# Power.net
KiCad netlist of a schematic drawn in Altium Designer
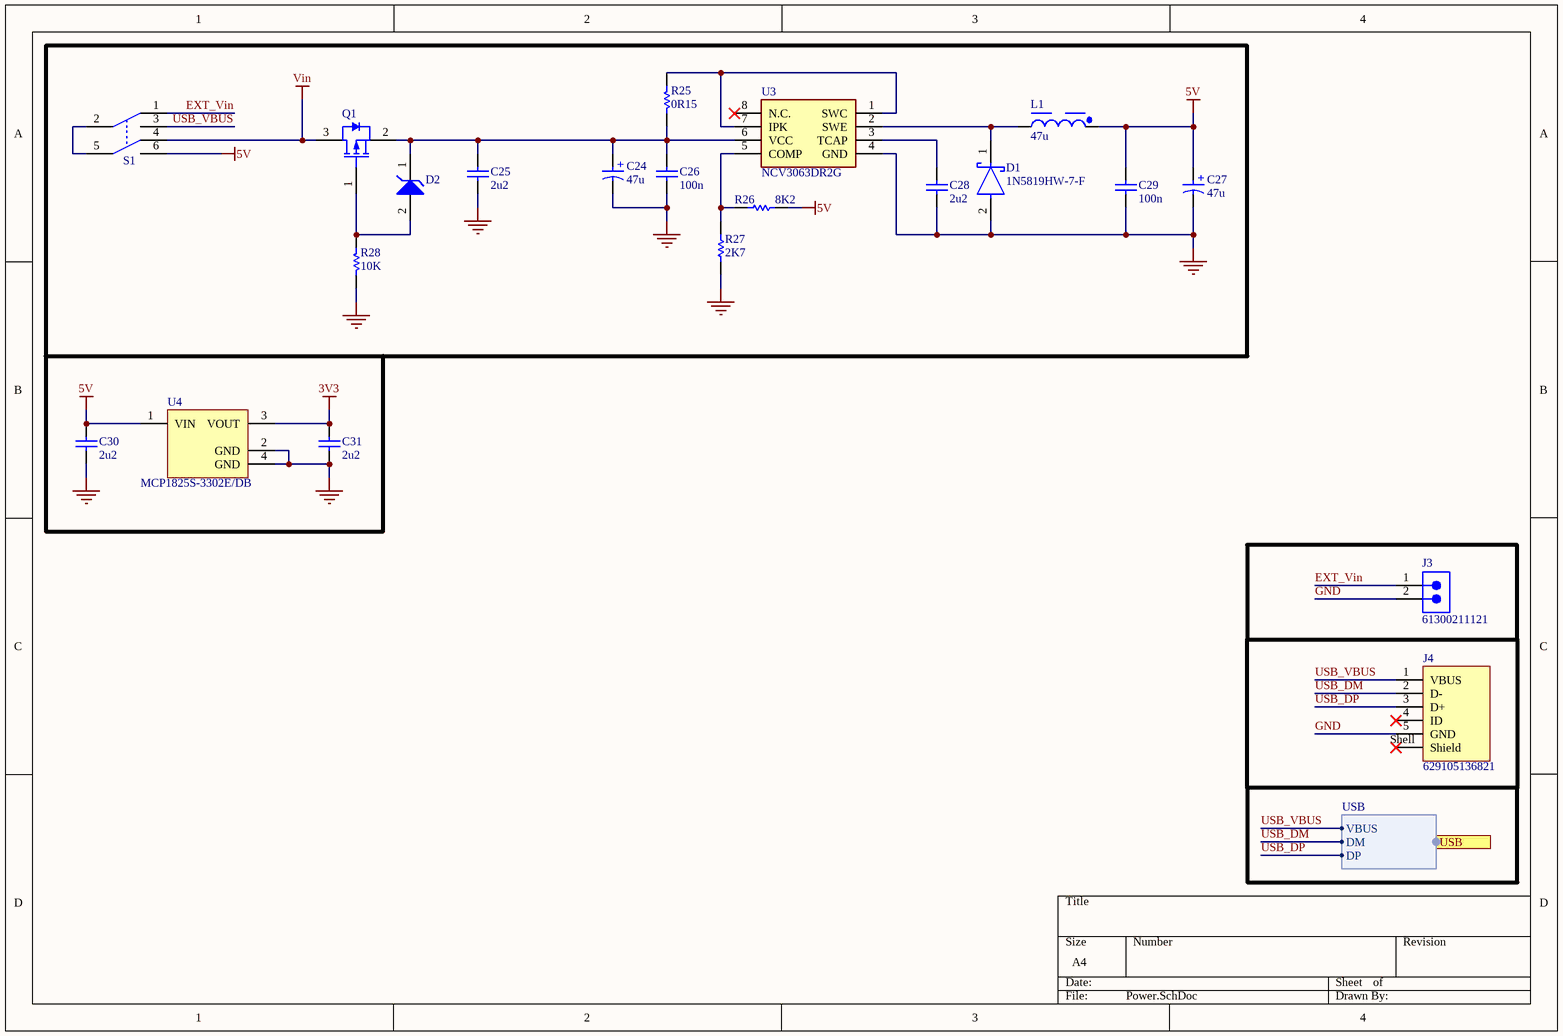
[diagram p0: Power.SchDoc]

(export (version "E")
  (design (tool "Eeschema 10.0.6"))
  (components
    (comp (ref "C24")
      (value "47u")
      (footprint "WCAP-ASLI_D6.3H7.7")
      (description "865080645012 WCAP-ASLI Aluminum Electrolytic Capacitors")
      (libsource (lib "Altium Content Vault") (part "Capacitor_Polarized"))
    )
    (comp (ref "C25")
      (value "2u2")
      (footprint "1206")
      (description "Capacitor 50V\r\n1206")
      (libsource (lib "Schlib1") (part "C1206C225K5RACAUTO7210"))
    )
    (comp (ref "C26")
      (value "100n")
      (footprint "0603")
      (description "Capacitor 50V\r\n0603")
      (libsource (lib "Schlib1") (part "GA0603Y104KXAAC31G"))
    )
    (comp (ref "C27")
      (value "47u")
      (footprint "WCAP-ASLI_D6.3H7.7")
      (description "865080645012 WCAP-ASLI Aluminum Electrolytic Capacitors")
      (libsource (lib "Altium Content Vault") (part "Capacitor_Polarized"))
    )
    (comp (ref "C28")
      (value "2u2")
      (footprint "1206")
      (description "Capacitor 50V\r\n1206")
      (libsource (lib "Schlib1") (part "C1206C225K5RACAUTO7210"))
    )
    (comp (ref "C29")
      (value "100n")
      (footprint "0603")
      (description "Capacitor 50V\r\n0603")
      (libsource (lib "Schlib1") (part "GA0603Y104KXAAC31G"))
    )
    (comp (ref "C30")
      (value "2u2")
      (footprint "1206")
      (description "Capacitor 50V\r\n1206")
      (libsource (lib "Schlib1") (part "C1206C225K5RACAUTO7210"))
    )
    (comp (ref "C31")
      (value "2u2")
      (footprint "1206")
      (description "Capacitor 50V\r\n1206")
      (libsource (lib "Schlib1") (part "C1206C225K5RACAUTO7210"))
    )
    (comp (ref "D1")
      (value "1N5819HW-7-F")
      (footprint "FP-SOD123-IPC_A")
      (description "DIODE SCHOTTKY 40V 1A SOD123")
      (libsource (lib "Altium Content Vault") (part "1d6ec82d83fb6aee721767c19dac4b9"))
    )
    (comp (ref "D2")
      (value "SZMMSZ4687T1G")
      (footprint "ONSC-SOD-123-2-425-04_V")
      (description "Zener Voltage Regulator, 500 mW, 2-Pin SOD-123, Pb-Free, Tape and Reel")
      (fields (field (name "MANUFACTURER") "On Semiconductor"))
      (libsource (lib "Altium Content Vault") (part "ONSC-K1A2-2"))
    )
    (comp (ref "J3")
      (value "61300211121")
      (footprint "61300211121")
      (libsource (lib "Altium Content Vault") (part "Header_Male_1R_02P"))
    )
    (comp (ref "J4")
      (value "629105136821")
      (footprint "629105136821")
      (libsource (lib "Altium Content Vault") (part "Micro USB 2.0_Type B_Receptacle_1 Port"))
    )
    (comp (ref "L1")
      (value "47u")
      (footprint "WE-HEPC_6030")
      (description "74408063470 Power Ind, 47Uh, Shielded, 0.8A Rohs Compliant: Yes")
      (libsource (lib "Altium Content Vault") (part "Inductor - 2"))
    )
    (comp (ref "Q1")
      (value "NTRV4101PT1G")
      (footprint "ONSC-SOT-23-3-318-08_V")
      (description "Trench Power MOSFET, -20 V, Single P-Channel, 3-Pin SOT-23, Pb-Free, Tape and Reel")
      (fields (field (name "MANUFACTURER") "On Semiconductor"))
      (libsource (lib "Altium Content Vault") (part "ONSC-PMOS-G1S2D3-3_D"))
    )
    (comp (ref "R25")
      (value "0R15")
      (footprint "1206")
      (description "Resistor 0.5W")
      (libsource (lib "Schlib1") (part "WFC1206R1500FE66"))
    )
    (comp (ref "R26")
      (value "8K2")
      (footprint "0603")
      (description "Resistor 0.1W")
      (libsource (lib "Schlib1") (part "CRCW06038K20FKEA"))
    )
    (comp (ref "R27")
      (value "2K7")
      (footprint "0603")
      (description "Resistor 0.1W")
      (libsource (lib "Schlib1") (part "CRCW06032K70FKEA"))
    )
    (comp (ref "R28")
      (value "10K")
      (footprint "0603")
      (description "Resistor 0.1W")
      (libsource (lib "Schlib1") (part "CRCW060310K0FKEA"))
    )
    (comp (ref "S1")
      (value "OS202013MT8QN1")
      (footprint "OS202013MT8QN1")
      (description "Switch")
      (fields (field (name "MOUSER PART NUMBER") "611-OS202013MT8QN1"))
      (libsource (lib "Schlib1") (part "OS202013MT8QN1"))
    )
    (comp (ref "U3")
      (value "NCV3063DR2G")
      (footprint "SamacSys:SOIC127P600X175-8N")
      (description "Integrated Circuit")
      (fields (field (name "MOUSER PART NUMBER") "863-NCV3063DR2G"))
      (libsource (lib "Schlib1") (part "NCV3063DR2G"))
    )
    (comp (ref "U4")
      (value "MCP1825S-3302E/DB")
      (footprint "SOT-223-DB3_N")
      (description "500 mA, Low Voltage, Low Quiescent Current LDO Regulator, 3-Pin SOT-223, Extended Temperature")
      (libsource (lib "Altium Content Vault") (part "PM-LINEREG-MCP1825-IL4"))
    )
  )
  (nets
    (net (code "2") (name "/EXT_Vin") (class "Default")
      (node (ref "J3") (pin "1") (pinfunction "1_1") (pintype "passive"))
      (node (ref "S1") (pin "1") (pinfunction "NC_1_1") (pintype "passive"))
    )
    (net (code "3") (name "/USB_DM") (class "Default")
      (node (ref "J4") (pin "2") (pinfunction "D-_2") (pintype "passive"))
    )
    (net (code "4") (name "/USB_DP") (class "Default")
      (node (ref "J4") (pin "3") (pinfunction "D+_3") (pintype "passive"))
    )
    (net (code "5") (name "/USB_VBUS") (class "Default")
      (node (ref "J4") (pin "1") (pinfunction "VBUS_1") (pintype "passive"))
      (node (ref "S1") (pin "3") (pinfunction "NO_1_3") (pintype "passive"))
    )
    (net (code "7") (name "3V3") (class "Default")
      (node (ref "C31") (pin "2") (pinfunction "2_2") (pintype "passive"))
      (node (ref "U4") (pin "3") (pinfunction "VOUT_3") (pintype "power_in"))
    )
    (net (code "8") (name "5V") (class "Default")
      (node (ref "C27") (pin "1") (pinfunction "P_1") (pintype "passive"))
      (node (ref "C29") (pin "2") (pinfunction "2_2") (pintype "passive"))
      (node (ref "C30") (pin "2") (pinfunction "2_2") (pintype "passive"))
      (node (ref "L1") (pin "1") (pinfunction "1_1") (pintype "passive"))
      (node (ref "R26") (pin "2") (pinfunction "2_2") (pintype "passive"))
      (node (ref "S1") (pin "6") (pinfunction "NO_2_6") (pintype "passive"))
      (node (ref "U4") (pin "1") (pinfunction "VIN_1") (pintype "power_in"))
    )
    (net (code "9") (name "GND") (class "Default")
      (node (ref "C24") (pin "2") (pinfunction "N_2") (pintype "passive"))
      (node (ref "C25") (pin "1") (pinfunction "1_1") (pintype "passive"))
      (node (ref "C26") (pin "1") (pinfunction "1_1") (pintype "passive"))
      (node (ref "C27") (pin "2") (pinfunction "N_2") (pintype "passive"))
      (node (ref "C28") (pin "1") (pinfunction "1_1") (pintype "passive"))
      (node (ref "C29") (pin "1") (pinfunction "1_1") (pintype "passive"))
      (node (ref "C30") (pin "1") (pinfunction "1_1") (pintype "passive"))
      (node (ref "C31") (pin "1") (pinfunction "1_1") (pintype "passive"))
      (node (ref "D1") (pin "2") (pinfunction "A_2") (pintype "passive"))
      (node (ref "J3") (pin "2") (pinfunction "2_2") (pintype "passive"))
      (node (ref "J4") (pin "5") (pinfunction "GND_5") (pintype "passive"))
      (node (ref "R27") (pin "1") (pinfunction "1_1") (pintype "passive"))
      (node (ref "R28") (pin "1") (pinfunction "1_1") (pintype "passive"))
      (node (ref "U3") (pin "4") (pinfunction "GND_4") (pintype "passive"))
      (node (ref "U4") (pin "2") (pinfunction "GND_2") (pintype "power_in"))
      (node (ref "U4") (pin "4") (pinfunction "GND_4") (pintype "power_in"))
    )
    (net (code "10") (name "Net-(C24-P)") (class "Default")
      (node (ref "C24") (pin "1") (pinfunction "P_1") (pintype "passive"))
      (node (ref "C25") (pin "2") (pinfunction "2_2") (pintype "passive"))
      (node (ref "C26") (pin "2") (pinfunction "2_2") (pintype "passive"))
      (node (ref "D2") (pin "1") (pinfunction "K_1") (pintype "passive"))
      (node (ref "Q1") (pin "2") (pinfunction "S_2") (pintype "passive"))
      (node (ref "R25") (pin "1") (pinfunction "1_1") (pintype "passive"))
      (node (ref "U3") (pin "6") (pinfunction "VCC_6") (pintype "passive"))
    )
    (net (code "11") (name "Net-(D1-C)") (class "Default")
      (node (ref "D1") (pin "1") (pinfunction "C_1") (pintype "passive"))
      (node (ref "L1") (pin "2") (pinfunction "2_2") (pintype "passive"))
      (node (ref "U3") (pin "2") (pinfunction "SWE_2") (pintype "passive"))
    )
    (net (code "12") (name "Net-(D2-A)") (class "Default")
      (node (ref "D2") (pin "2") (pinfunction "A_2") (pintype "passive"))
      (node (ref "Q1") (pin "1") (pinfunction "G_1") (pintype "passive"))
      (node (ref "R28") (pin "2") (pinfunction "2_2") (pintype "passive"))
    )
    (net (code "13") (name "Net-(S1-COM_1)") (class "Default")
      (node (ref "S1") (pin "2") (pinfunction "COM_1_2") (pintype "passive"))
      (node (ref "S1") (pin "5") (pinfunction "COM_2_5") (pintype "passive"))
    )
    (net (code "14") (name "Net-(U3-COMP)") (class "Default")
      (node (ref "R26") (pin "1") (pinfunction "1_1") (pintype "passive"))
      (node (ref "R27") (pin "2") (pinfunction "2_2") (pintype "passive"))
      (node (ref "U3") (pin "5") (pinfunction "COMP_5") (pintype "passive"))
    )
    (net (code "15") (name "Net-(U3-IPK)") (class "Default")
      (node (ref "R25") (pin "2") (pinfunction "2_2") (pintype "passive"))
      (node (ref "U3") (pin "1") (pinfunction "SWC_1") (pintype "passive"))
      (node (ref "U3") (pin "7") (pinfunction "IPK_7") (pintype "passive"))
    )
    (net (code "16") (name "Net-(U3-TCAP)") (class "Default")
      (node (ref "C28") (pin "2") (pinfunction "2_2") (pintype "passive"))
      (node (ref "U3") (pin "3") (pinfunction "TCAP_3") (pintype "passive"))
    )
    (net (code "17") (name "Vin") (class "Default")
      (node (ref "Q1") (pin "3") (pinfunction "D_3") (pintype "passive"))
      (node (ref "S1") (pin "4") (pinfunction "NC_2_4") (pintype "passive"))
    )
    (net (code "18") (name "unconnected-(J4-ID-Pad4)") (class "Default")
      (node (ref "J4") (pin "4") (pinfunction "ID_4") (pintype "passive+no_connect"))
    )
    (net (code "19") (name "unconnected-(J4-Shield-PadShell)") (class "Default")
      (node (ref "J4") (pin "Shell") (pinfunction "Shield_Shell") (pintype "passive+no_connect"))
    )
    (net (code "20") (name "unconnected-(U3-N.C.-Pad8)") (class "Default")
      (node (ref "U3") (pin "8") (pinfunction "N.C._8") (pintype "passive+no_connect"))
    )
  )
)
